# XO345-1A.net
KiCad netlist of a schematic drawn in EAGLE
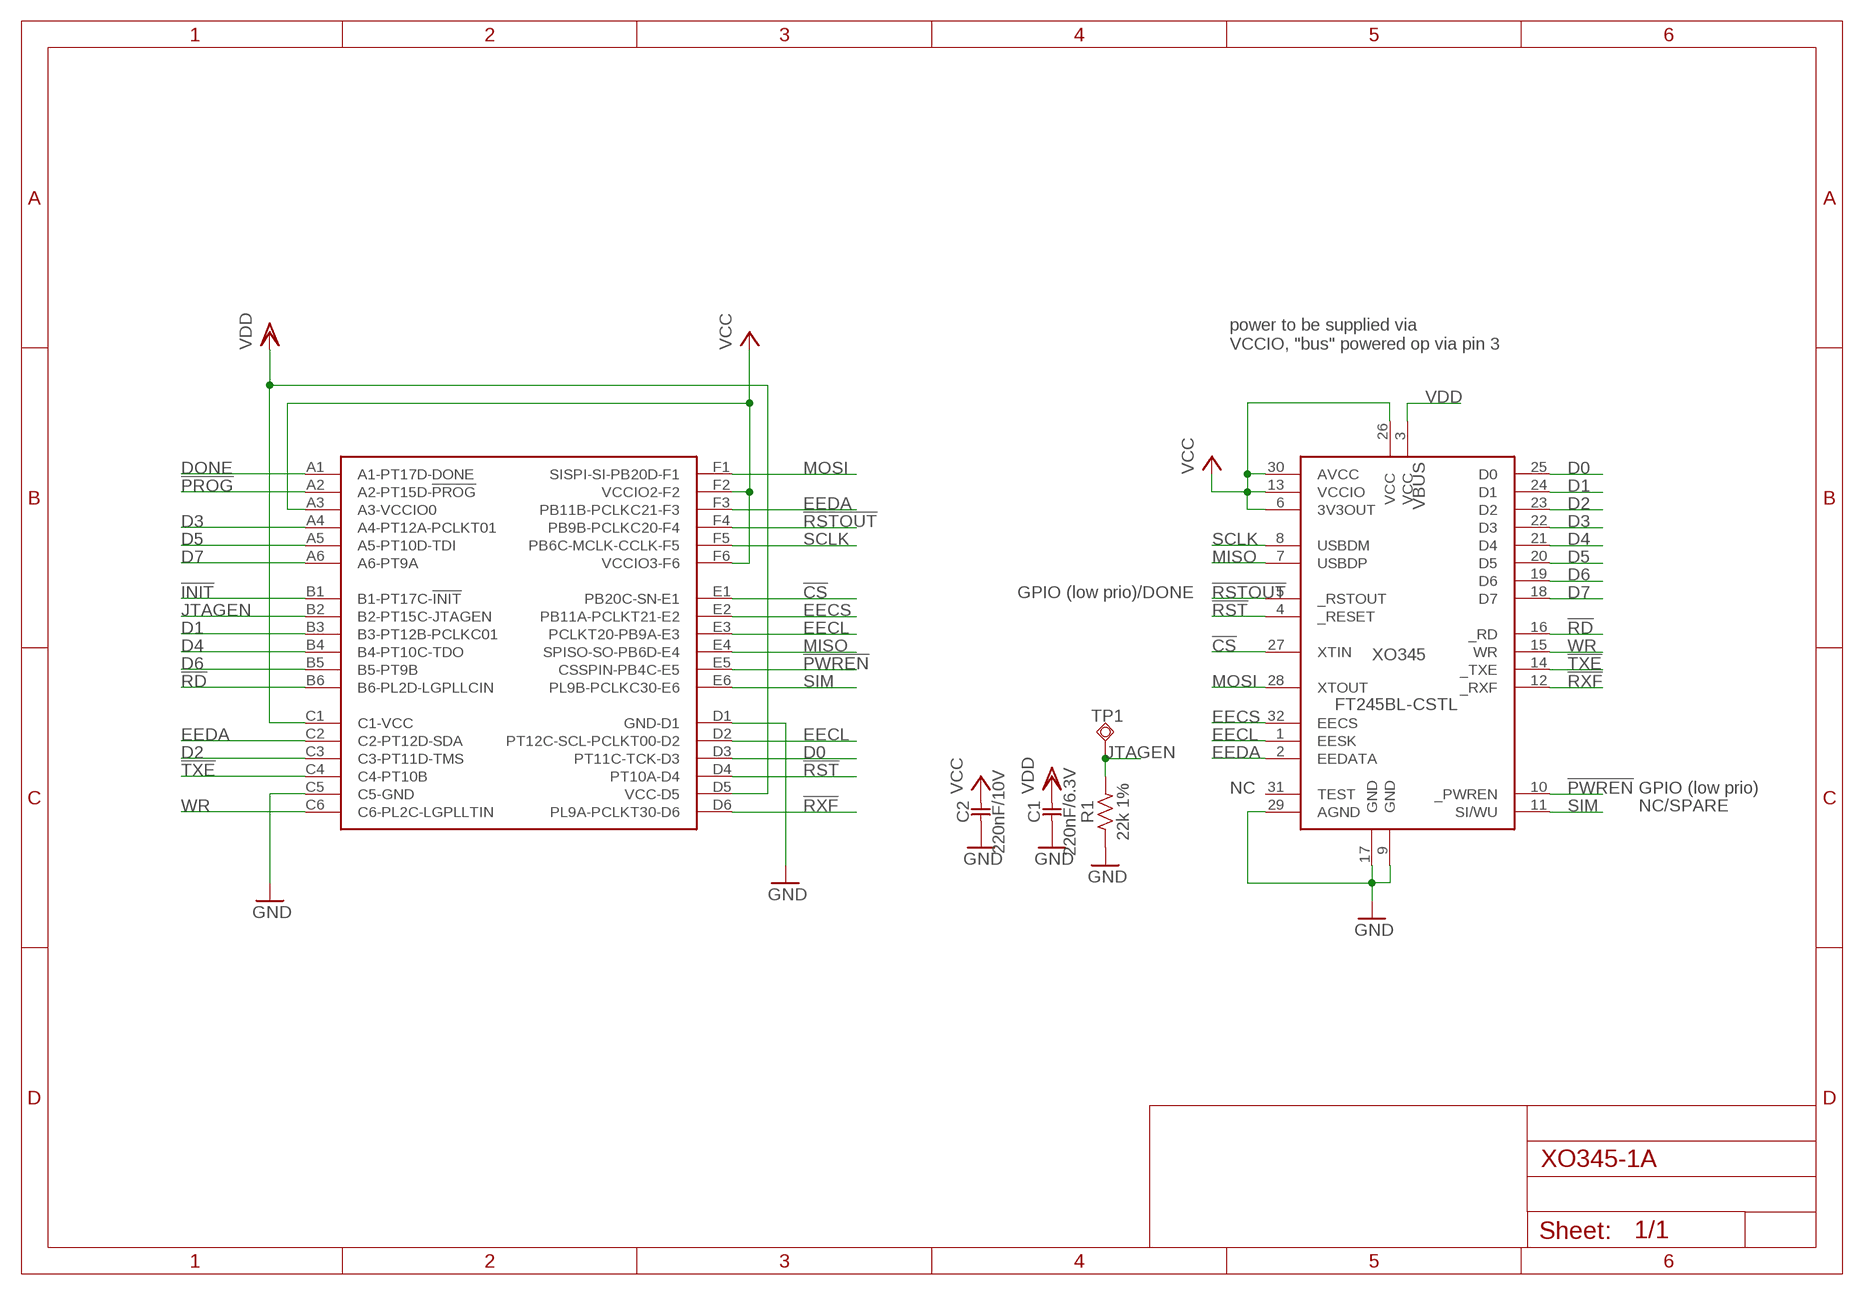
[diagram p0: schematic, sheet 1]

(export (version "E")
  (design (tool "Eeschema 10.0.6"))
  (components
    (comp (ref "C1")
      (value "220nF/6.3V")
      (footprint "eagle-import:C0402")
      (fields (field (name "MF") "TDK") (field (name "MFG_PARTNO") "C1005X5R1A224M050BC"))
      (libsource (lib "eagle-import") (part "CAP_0402"))
    )
    (comp (ref "C2")
      (value "220nF/10V")
      (footprint "eagle-import:C0603")
      (libsource (lib "eagle-import") (part "CAP_0603"))
    )
    (comp (ref "IC")
      (value "XO3-LCSP36")
      (footprint "eagle-import:WLCSP36")
      (fields
        (field (name "MF") "Lattice Semiconductor")
        (field (name "MFG_PARTNO") "LCMXO3L-1300E-5UWG36CTR50")
      )
      (libsource (lib "eagle-import") (part "XO3-LCSP36"))
    )
    (comp (ref "R1")
      (value "22k 1%")
      (footprint "eagle-import:R0402")
      (fields (field (name "MF") "Vishay") (field (name "MFG_PARTNO") "CRCW04022K70FKED"))
      (libsource (lib "eagle-import") (part "RES_0402"))
    )
    (comp (ref "TP1")
      (value "TPSQTP06R")
      (footprint "eagle-import:TP06R")
      (libsource (lib "eagle-import") (part "TPSQTP06R"))
    )
    (comp (ref "XO345")
      (value "FT245BL-CSTL")
      (footprint "eagle-import:LQFP-32-CAST")
      (libsource (lib "eagle-import") (part "FT245BL-CSTL"))
    )
  )
  (nets
    (net (code "1") (name "/D0") (class "Default")
      (node (ref "IC") (pin "D3") (pinfunction "PT11C-TCK-D3_D3") (pintype "bidirectional"))
      (node (ref "XO345") (pin "25") (pinfunction "D0_25") (pintype "bidirectional"))
    )
    (net (code "2") (name "/D1") (class "Default")
      (node (ref "IC") (pin "B3") (pinfunction "B3-PT12B-PCLKC01_B3") (pintype "bidirectional"))
      (node (ref "XO345") (pin "24") (pinfunction "D1_24") (pintype "bidirectional"))
    )
    (net (code "3") (name "/D2") (class "Default")
      (node (ref "IC") (pin "C3") (pinfunction "C3-PT11D-TMS_C3") (pintype "bidirectional"))
      (node (ref "XO345") (pin "23") (pinfunction "D2_23") (pintype "bidirectional"))
    )
    (net (code "4") (name "/D3") (class "Default")
      (node (ref "IC") (pin "A4") (pinfunction "A4-PT12A-PCLKT01_A4") (pintype "bidirectional"))
      (node (ref "XO345") (pin "22") (pinfunction "D3_22") (pintype "bidirectional"))
    )
    (net (code "5") (name "/D4") (class "Default")
      (node (ref "IC") (pin "B4") (pinfunction "B4-PT10C-TDO_B4") (pintype "bidirectional"))
      (node (ref "XO345") (pin "21") (pinfunction "D4_21") (pintype "bidirectional"))
    )
    (net (code "6") (name "/D5") (class "Default")
      (node (ref "IC") (pin "A5") (pinfunction "A5-PT10D-TDI_A5") (pintype "bidirectional"))
      (node (ref "XO345") (pin "20") (pinfunction "D5_20") (pintype "bidirectional"))
    )
    (net (code "7") (name "/D6") (class "Default")
      (node (ref "IC") (pin "B5") (pinfunction "B5-PT9B_B5") (pintype "bidirectional"))
      (node (ref "XO345") (pin "19") (pinfunction "D6_19") (pintype "bidirectional"))
    )
    (net (code "8") (name "/D7") (class "Default")
      (node (ref "IC") (pin "A6") (pinfunction "A6-PT9A_A6") (pintype "bidirectional"))
      (node (ref "XO345") (pin "18") (pinfunction "D7_18") (pintype "bidirectional"))
    )
    (net (code "9") (name "/DONE") (class "Default")
      (node (ref "IC") (pin "A1") (pinfunction "A1-PT17D-DONE_A1") (pintype "bidirectional"))
    )
    (net (code "10") (name "/EECL") (class "Default")
      (node (ref "IC") (pin "D2") (pinfunction "PT12C-SCL-PCLKT00-D2_D2") (pintype "bidirectional"))
      (node (ref "IC") (pin "E3") (pinfunction "PCLKT20-PB9A-E3_E3") (pintype "bidirectional"))
      (node (ref "XO345") (pin "1") (pinfunction "EESK_1") (pintype "output"))
    )
    (net (code "11") (name "/EECS") (class "Default")
      (node (ref "IC") (pin "E2") (pinfunction "PB11A-PCLKT21-E2_E2") (pintype "bidirectional"))
      (node (ref "XO345") (pin "32") (pinfunction "EECS_32") (pintype "bidirectional"))
    )
    (net (code "12") (name "/EEDA") (class "Default")
      (node (ref "IC") (pin "C2") (pinfunction "C2-PT12D-SDA_C2") (pintype "bidirectional"))
      (node (ref "IC") (pin "F3") (pinfunction "PB11B-PCLKC21-F3_F3") (pintype "bidirectional"))
      (node (ref "XO345") (pin "2") (pinfunction "EEDATA_2") (pintype "bidirectional"))
    )
    (net (code "13") (name "/JTAGEN") (class "Default")
      (node (ref "IC") (pin "B2") (pinfunction "B2-PT15C-JTAGEN_B2") (pintype "bidirectional"))
      (node (ref "R1") (pin "2") (pinfunction "2_2") (pintype "passive"))
      (node (ref "TP1") (pin "TP") (pinfunction "TP_TP") (pintype "input"))
    )
    (net (code "14") (name "/MISO") (class "Default")
      (node (ref "IC") (pin "E4") (pinfunction "SPISO-SO-PB6D-E4_E4") (pintype "bidirectional"))
      (node (ref "XO345") (pin "7") (pinfunction "USBDP_7") (pintype "bidirectional"))
    )
    (net (code "15") (name "/MOSI") (class "Default")
      (node (ref "IC") (pin "F1") (pinfunction "SISPI-SI-PB20D-F1_F1") (pintype "bidirectional"))
      (node (ref "XO345") (pin "28") (pinfunction "XTOUT_28") (pintype "output"))
    )
    (net (code "16") (name "/SCLK") (class "Default")
      (node (ref "IC") (pin "F5") (pinfunction "PB6C-MCLK-CCLK-F5_F5") (pintype "bidirectional"))
      (node (ref "XO345") (pin "8") (pinfunction "USBDM_8") (pintype "bidirectional"))
    )
    (net (code "17") (name "/SIM") (class "Default")
      (node (ref "IC") (pin "E6") (pinfunction "PL9B-PCLKC30-E6_E6") (pintype "bidirectional"))
      (node (ref "XO345") (pin "11") (pinfunction "SI/WU_11") (pintype "input"))
    )
    (net (code "18") (name "/WR") (class "Default")
      (node (ref "IC") (pin "C6") (pinfunction "C6-PL2C-LGPLLTIN_C6") (pintype "bidirectional"))
      (node (ref "XO345") (pin "15") (pinfunction "WR_15") (pintype "input"))
    )
    (net (code "19") (name "/~{CS}") (class "Default")
      (node (ref "IC") (pin "E1") (pinfunction "PB20C-SN-E1_E1") (pintype "bidirectional"))
      (node (ref "XO345") (pin "27") (pinfunction "XTIN_27") (pintype "input"))
    )
    (net (code "20") (name "/~{INIT}") (class "Default")
      (node (ref "IC") (pin "B1") (pinfunction "B1-PT17C-~{INIT}_B1") (pintype "bidirectional"))
    )
    (net (code "21") (name "/~{PROG}") (class "Default")
      (node (ref "IC") (pin "A2") (pinfunction "A2-PT15D-~{PROG}_A2") (pintype "bidirectional"))
    )
    (net (code "22") (name "/~{PWREN}") (class "Default")
      (node (ref "IC") (pin "E5") (pinfunction "CSSPIN-PB4C-E5_E5") (pintype "bidirectional"))
      (node (ref "XO345") (pin "10") (pinfunction "_PWREN_10") (pintype "output"))
    )
    (net (code "23") (name "/~{RD}") (class "Default")
      (node (ref "IC") (pin "B6") (pinfunction "B6-PL2D-LGPLLCIN_B6") (pintype "bidirectional"))
      (node (ref "XO345") (pin "16") (pinfunction "_RD_16") (pintype "input"))
    )
    (net (code "24") (name "/~{RSTOUT}") (class "Default")
      (node (ref "IC") (pin "F4") (pinfunction "PB9B-PCLKC20-F4_F4") (pintype "bidirectional"))
      (node (ref "XO345") (pin "5") (pinfunction "_RSTOUT_5") (pintype "output"))
    )
    (net (code "25") (name "/~{RST}") (class "Default")
      (node (ref "IC") (pin "D4") (pinfunction "PT10A-D4_D4") (pintype "bidirectional"))
      (node (ref "XO345") (pin "4") (pinfunction "_RESET_4") (pintype "input"))
    )
    (net (code "26") (name "/~{RXF}") (class "Default")
      (node (ref "IC") (pin "D6") (pinfunction "PL9A-PCLKT30-D6_D6") (pintype "bidirectional"))
      (node (ref "XO345") (pin "12") (pinfunction "_RXF_12") (pintype "output"))
    )
    (net (code "27") (name "/~{TXE}") (class "Default")
      (node (ref "IC") (pin "C4") (pinfunction "C4-PT10B_C4") (pintype "bidirectional"))
      (node (ref "XO345") (pin "14") (pinfunction "_TXE_14") (pintype "output"))
    )
    (net (code "28") (name "GND") (class "Default")
      (node (ref "C1") (pin "1") (pinfunction "1_1") (pintype "passive"))
      (node (ref "C2") (pin "1") (pinfunction "1_1") (pintype "passive"))
      (node (ref "IC") (pin "C5") (pinfunction "C5-GND_C5") (pintype "bidirectional"))
      (node (ref "IC") (pin "D1") (pinfunction "GND-D1_D1") (pintype "bidirectional"))
      (node (ref "R1") (pin "1") (pinfunction "1_1") (pintype "passive"))
      (node (ref "XO345") (pin "17") (pinfunction "GND_17") (pintype "power_in"))
      (node (ref "XO345") (pin "29") (pinfunction "AGND_29") (pintype "power_in"))
      (node (ref "XO345") (pin "9") (pinfunction "GND_9") (pintype "power_in"))
    )
    (net (code "29") (name "VCC") (class "Default")
      (node (ref "C2") (pin "2") (pinfunction "2_2") (pintype "passive"))
      (node (ref "IC") (pin "A3") (pinfunction "A3-VCCIO0_A3") (pintype "bidirectional"))
      (node (ref "IC") (pin "F2") (pinfunction "VCCIO2-F2_F2") (pintype "bidirectional"))
      (node (ref "IC") (pin "F6") (pinfunction "VCCIO3-F6_F6") (pintype "bidirectional"))
      (node (ref "XO345") (pin "13") (pinfunction "VCCIO_13") (pintype "power_in"))
      (node (ref "XO345") (pin "26") (pinfunction "VCC_26") (pintype "power_in"))
      (node (ref "XO345") (pin "30") (pinfunction "AVCC_30") (pintype "power_in"))
      (node (ref "XO345") (pin "6") (pinfunction "3V3OUT_6") (pintype "output"))
    )
    (net (code "30") (name "VDD") (class "Default")
      (node (ref "C1") (pin "2") (pinfunction "2_2") (pintype "passive"))
      (node (ref "IC") (pin "C1") (pinfunction "C1-VCC_C1") (pintype "bidirectional"))
      (node (ref "IC") (pin "D5") (pinfunction "VCC-D5_D5") (pintype "bidirectional"))
      (node (ref "XO345") (pin "3") (pinfunction "VCC_3") (pintype "power_in"))
    )
    (net (code "31") (name "unconnected-(XO345-TEST-Pad31)") (class "Default")
      (node (ref "XO345") (pin "31") (pinfunction "TEST_31") (pintype "input"))
    )
  )
)
